# 02_LoRaE5_MCU.net
KiCad netlist of a schematic drawn in Altium Designer
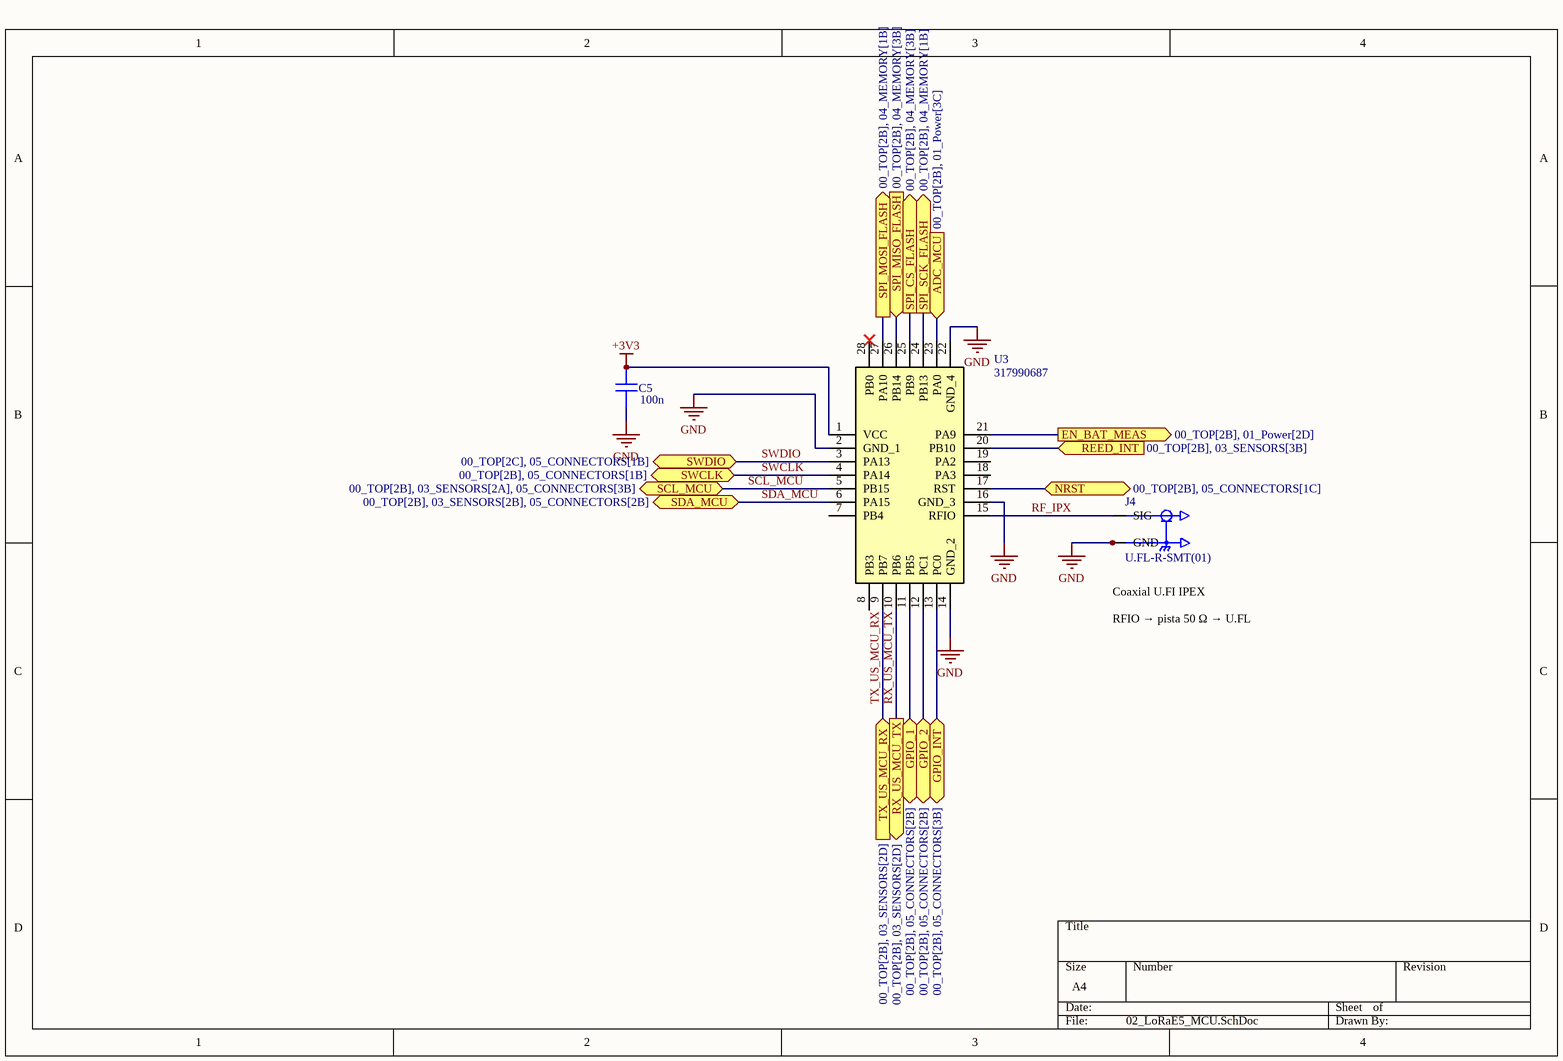
[diagram p0: 02_LoRaE5_MCU.SchDoc]

(export (version "E")
  (design (tool "Eeschema 10.0.6"))
  (components
    (comp (ref "C5")
      (value "100n")
      (footprint "Capacitor_SMD:0603_1608m")
      (libsource (lib "TrashTrack_SCH_LIB") (part "Generic_Capacitor"))
    )
    (comp (ref "J4")
      (value "U.FL-R-SMT(01)")
      (footprint "U.FL-R-SMT(01)")
      (fields (field (name "MF") "Hirose"))
      (libsource (lib "TrashTrack_SCH_LIB") (part "U.FL-R-SMT(01)"))
    )
    (comp (ref "U3")
      (value "317990687")
      (footprint "317990687")
      (libsource (lib "TrashTrack_SCH_LIB") (part "317990687"))
    )
  )
  (nets
    (net (code "1") (name "+3V3") (class "Default")
      (node (ref "C5") (pin "1") (pintype "passive"))
      (node (ref "U3") (pin "1") (pinfunction "VCC_1") (pintype "passive"))
    )
    (net (code "2") (name "/ADC_MCU") (class "Default")
      (node (ref "U3") (pin "23") (pinfunction "PA0_23") (pintype "passive"))
    )
    (net (code "3") (name "/EN_BAT_MEAS") (class "Default")
      (node (ref "U3") (pin "21") (pinfunction "PA9_21") (pintype "passive"))
    )
    (net (code "4") (name "/GPIO_1") (class "Default")
      (node (ref "U3") (pin "11") (pinfunction "PB5_11") (pintype "passive"))
    )
    (net (code "5") (name "/GPIO_2") (class "Default")
      (node (ref "U3") (pin "12") (pinfunction "PC1_12") (pintype "passive"))
    )
    (net (code "6") (name "/GPIO_INT") (class "Default")
      (node (ref "U3") (pin "13") (pinfunction "PC0_13") (pintype "passive"))
    )
    (net (code "7") (name "/NRST") (class "Default")
      (node (ref "U3") (pin "17") (pinfunction "RST_17") (pintype "passive"))
    )
    (net (code "8") (name "/REED_INT") (class "Default")
      (node (ref "U3") (pin "20") (pinfunction "PB10_20") (pintype "passive"))
    )
    (net (code "9") (name "/RF_IPX") (class "Default")
      (node (ref "J4") (pin "3") (pinfunction "SIG_3") (pintype "passive"))
      (node (ref "U3") (pin "15") (pinfunction "RFIO_15") (pintype "passive"))
    )
    (net (code "10") (name "/RX_US_MCU_TX") (class "Default")
      (node (ref "U3") (pin "10") (pinfunction "PB6_10") (pintype "passive"))
    )
    (net (code "11") (name "/SCL_MCU") (class "Default")
      (node (ref "U3") (pin "5") (pinfunction "PB15_5") (pintype "passive"))
    )
    (net (code "12") (name "/SDA_MCU") (class "Default")
      (node (ref "U3") (pin "6") (pinfunction "PA15_6") (pintype "passive"))
    )
    (net (code "13") (name "/SPI_CS_FLASH") (class "Default")
      (node (ref "U3") (pin "25") (pinfunction "PB9_25") (pintype "passive"))
    )
    (net (code "14") (name "/SPI_MISO_FLASH") (class "Default")
      (node (ref "U3") (pin "26") (pinfunction "PB14_26") (pintype "passive"))
    )
    (net (code "15") (name "/SPI_MOSI_FLASH") (class "Default")
      (node (ref "U3") (pin "27") (pinfunction "PA10_27") (pintype "passive"))
    )
    (net (code "16") (name "/SPI_SCK_FLASH") (class "Default")
      (node (ref "U3") (pin "24") (pinfunction "PB13_24") (pintype "passive"))
    )
    (net (code "17") (name "/SWCLK") (class "Default")
      (node (ref "U3") (pin "4") (pinfunction "PA14_4") (pintype "passive"))
    )
    (net (code "18") (name "/SWDIO") (class "Default")
      (node (ref "U3") (pin "3") (pinfunction "PA13_3") (pintype "passive"))
    )
    (net (code "19") (name "/TX_US_MCU_RX") (class "Default")
      (node (ref "U3") (pin "9") (pinfunction "PB7_9") (pintype "passive"))
    )
    (net (code "20") (name "GND") (class "Default")
      (node (ref "C5") (pin "2") (pintype "passive"))
      (node (ref "J4") (pin "1") (pinfunction "GND_1") (pintype "passive"))
      (node (ref "J4") (pin "2") (pinfunction "GND_2") (pintype "passive"))
      (node (ref "U3") (pin "14") (pinfunction "GND_2_14") (pintype "passive"))
      (node (ref "U3") (pin "16") (pinfunction "GND_3_16") (pintype "passive"))
      (node (ref "U3") (pin "2") (pinfunction "GND_1_2") (pintype "passive"))
      (node (ref "U3") (pin "22") (pinfunction "GND_4_22") (pintype "passive"))
    )
    (net (code "21") (name "unconnected-(U3-PA2-Pad19)") (class "Default")
      (node (ref "U3") (pin "19") (pinfunction "PA2_19") (pintype "passive"))
    )
    (net (code "22") (name "unconnected-(U3-PA3-Pad18)") (class "Default")
      (node (ref "U3") (pin "18") (pinfunction "PA3_18") (pintype "passive"))
    )
    (net (code "23") (name "unconnected-(U3-PB0-Pad28)") (class "Default")
      (node (ref "U3") (pin "28") (pinfunction "PB0_28") (pintype "passive+no_connect"))
    )
    (net (code "24") (name "unconnected-(U3-PB3-Pad8)") (class "Default")
      (node (ref "U3") (pin "8") (pinfunction "PB3_8") (pintype "passive"))
    )
    (net (code "25") (name "unconnected-(U3-PB4-Pad7)") (class "Default")
      (node (ref "U3") (pin "7") (pinfunction "PB4_7") (pintype "passive"))
    )
  )
)
